# SCH_open_temperature_sensor_2023-12-14.net
KiCad netlist of a schematic drawn in EasyEDA
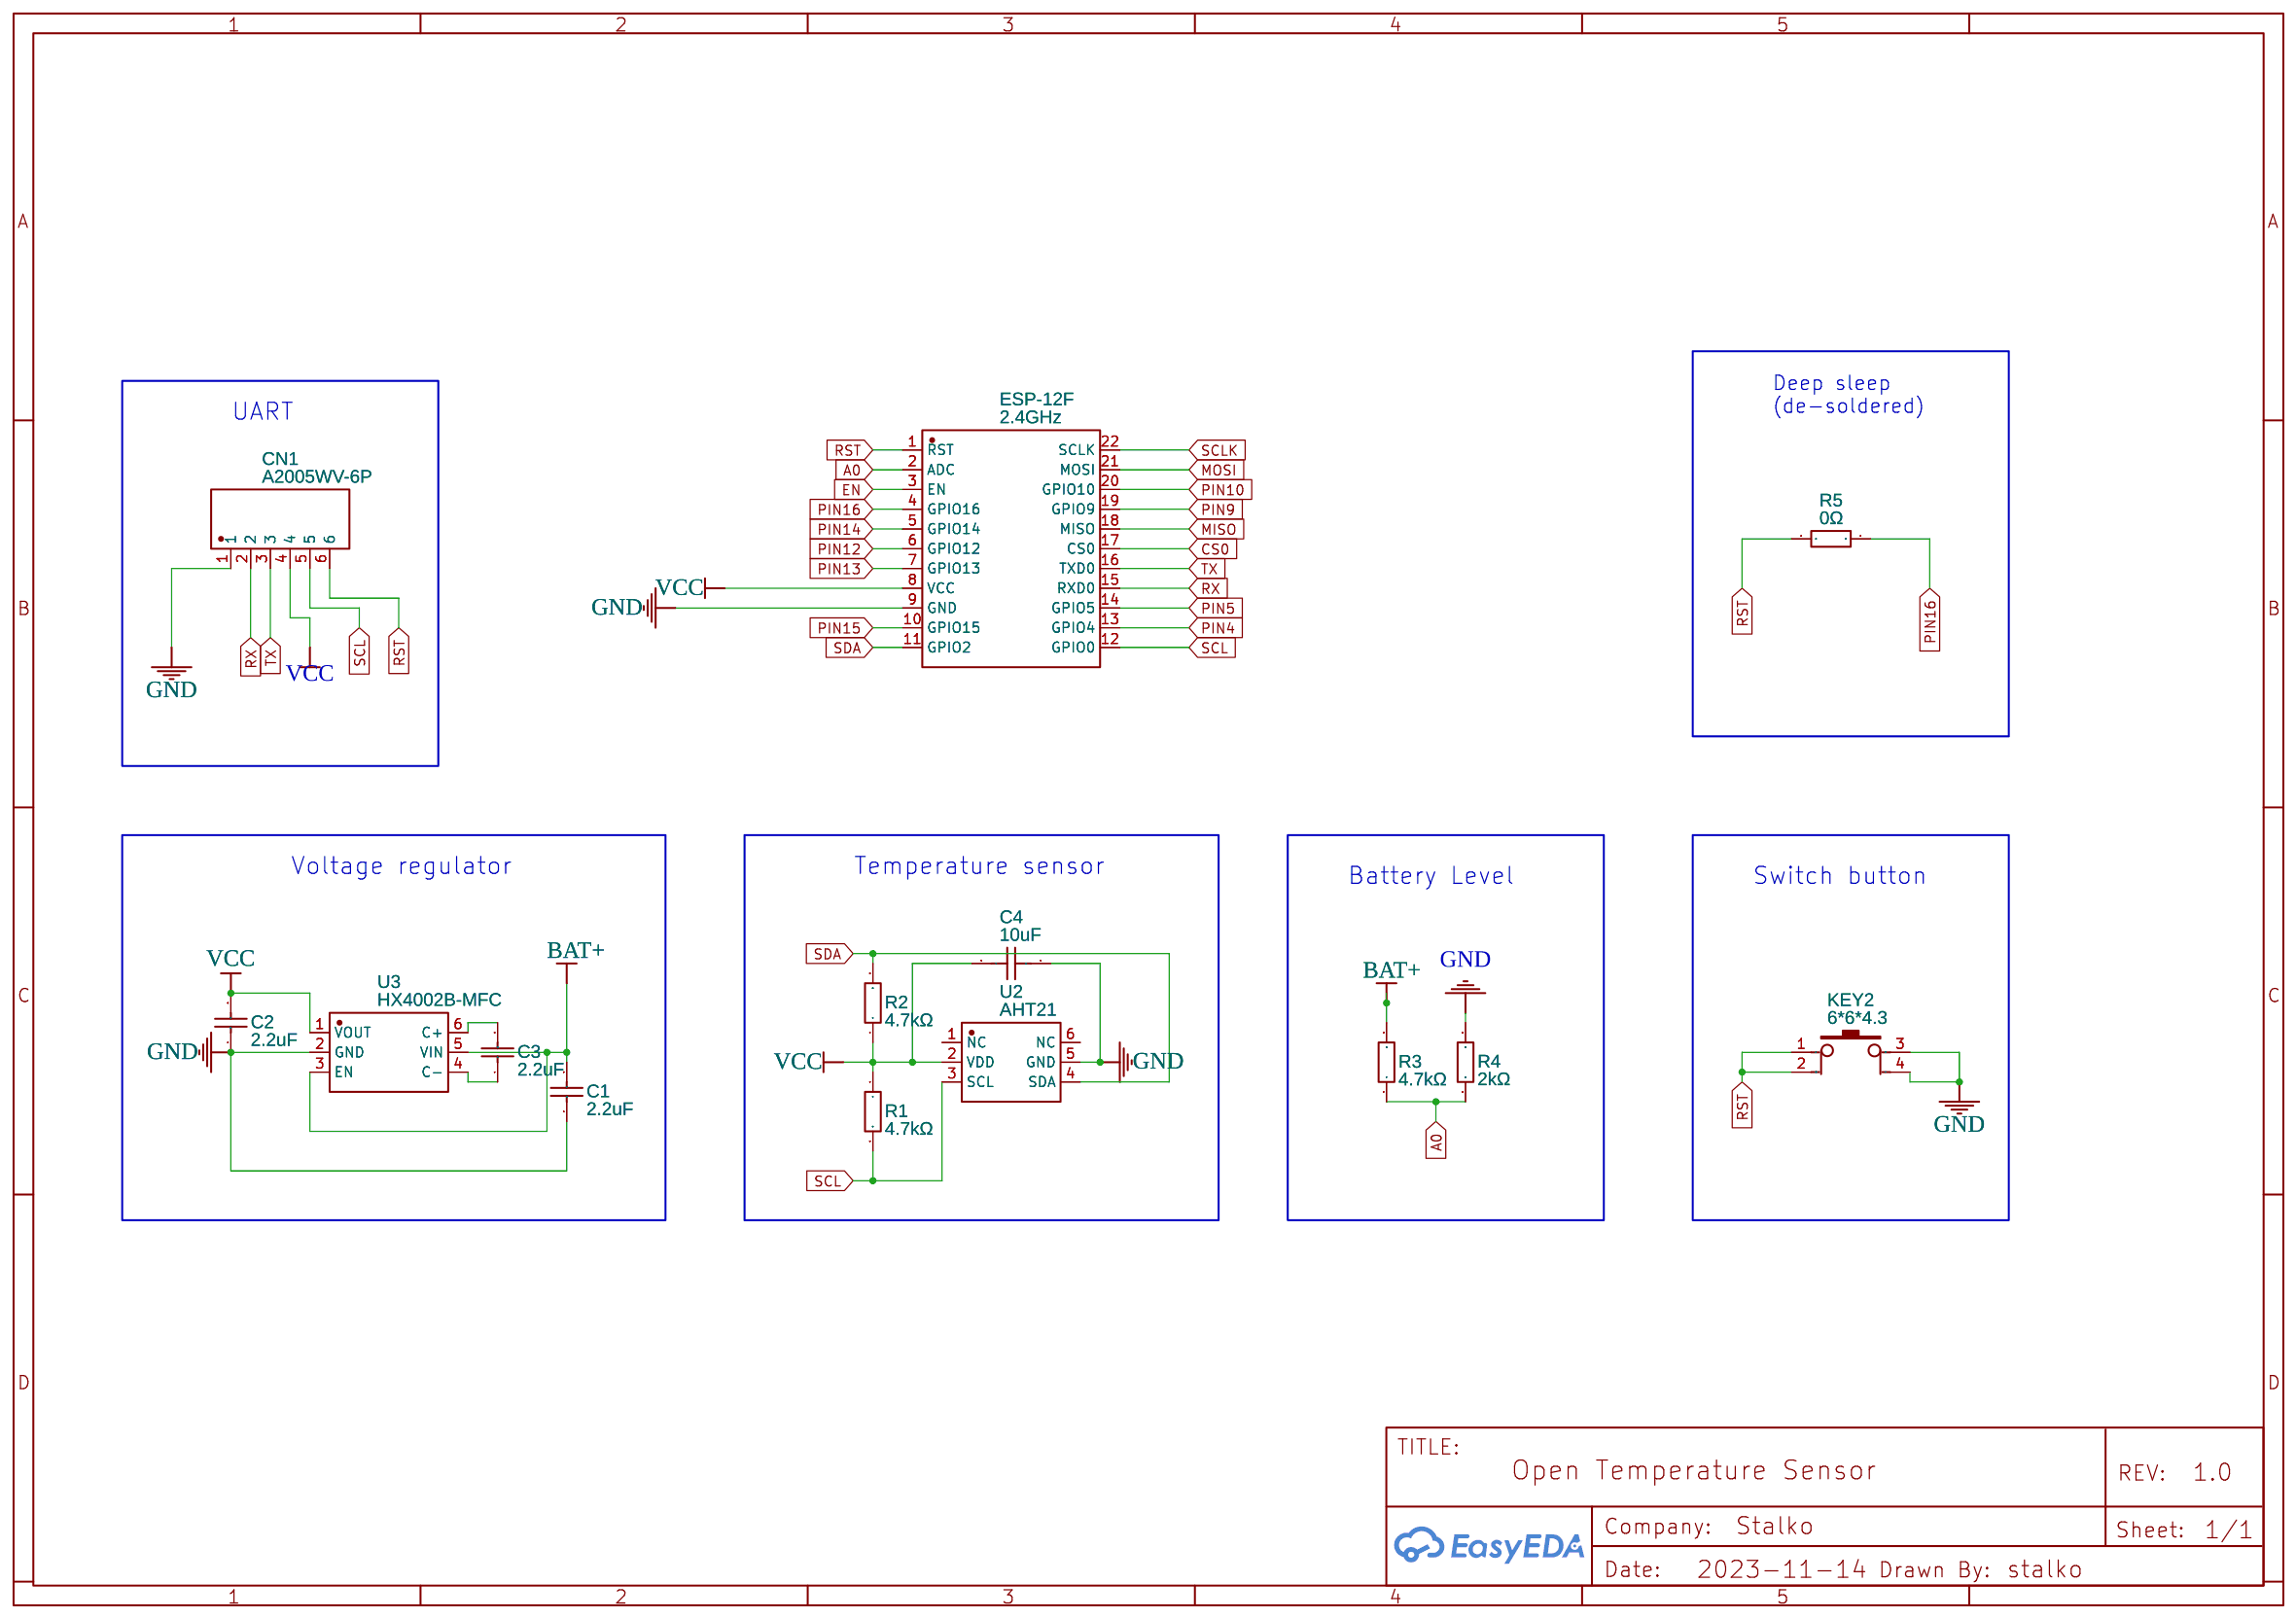
[diagram p0: schematic sheet]

(export (version "E")
  (design (tool "Eeschema 10.0.6"))
  (components
    (comp (ref "C1")
      (value "2.2uF")
      (fields
        (field (name "Manufacturer Part") "CC0805ZKY5V8BB225")
        (field (name "Manufacturer") "YAGEO(国巨)")
      )
      (libsource (lib "") (part "CC0805ZKY5V8BB225"))
    )
    (comp (ref "C2")
      (value "2.2uF")
      (fields
        (field (name "Manufacturer Part") "CC0805ZKY5V8BB225")
        (field (name "Manufacturer") "YAGEO(国巨)")
      )
      (libsource (lib "") (part "CC0805ZKY5V8BB225"))
    )
    (comp (ref "C3")
      (value "2.2uF")
      (fields
        (field (name "Manufacturer Part") "CC0805ZKY5V8BB225")
        (field (name "Manufacturer") "YAGEO(国巨)")
      )
      (libsource (lib "") (part "CC0805ZKY5V8BB225"))
    )
    (comp (ref "C4")
      (value "10uF")
      (fields
        (field (name "Manufacturer Part") "CC0805KKX7R7BB106")
        (field (name "Manufacturer") "YAGEO(国巨)")
      )
      (libsource (lib "") (part "CC0805KKX7R7BB106"))
    )
    (comp (ref "CN1")
      (value "A2005WV-6P")
      (fields (field (name "Manufacturer") "CJT(长江连接器)"))
      (libsource (lib "") (part "A2005WV-6P"))
    )
    (comp (ref "ESP-12F")
      (value "2.4GHz")
      (fields
        (field (name "Manufacturer Part") "ESP-12F(ESP8266MOD)")
        (field (name "Manufacturer") "Ai-Thinker(安信可)")
      )
      (libsource (lib "") (part "ESP-12F(ESP8266MOD)"))
    )
    (comp (ref "KEY2")
      (value "6*6*4.3")
      (fields (field (name "Manufacturer") "ReliaPro"))
      (libsource (lib "") (part "6*6*4.3"))
    )
    (comp (ref "R1")
      (value "4.7kΩ")
      (fields (field (name "Manufacturer Part") "RMC08054.7K5%N") (field (name "Manufacturer") "Tyohm(幸亚电阻)"))
      (libsource (lib "") (part "RMC08054.7K5%N_2"))
    )
    (comp (ref "R2")
      (value "4.7kΩ")
      (fields (field (name "Manufacturer Part") "RMC08054.7K5%N") (field (name "Manufacturer") "Tyohm(幸亚电阻)"))
      (libsource (lib "") (part "RMC08054.7K5%N"))
    )
    (comp (ref "R3")
      (value "4.7kΩ")
      (fields (field (name "Manufacturer Part") "RMC08054.7K5%N") (field (name "Manufacturer") "Tyohm(幸亚电阻)"))
      (libsource (lib "") (part "RMC08054.7K5%N"))
    )
    (comp (ref "R4")
      (value "2kΩ")
      (fields (field (name "Manufacturer Part") "CR0805F82371G") (field (name "Manufacturer") "LIZ(丽智电子)"))
      (libsource (lib "") (part "CR0805F82371G"))
    )
    (comp (ref "R5")
      (value "0Ω")
      (fields (field (name "Manufacturer Part") "RMC08054.7K5%N") (field (name "Manufacturer") "Tyohm(幸亚电阻)"))
      (libsource (lib "") (part "RMC08054.7K5%N_1"))
    )
    (comp (ref "U2")
      (value "AHT21")
      (fields (field (name "Manufacturer") "广州奥松"))
      (libsource (lib "") (part "AHT21"))
    )
    (comp (ref "U3") (value "HX4002B-MFC") (libsource (lib "") (part "HX4002B-MFC")))
  )
  (nets
    (net (code "1") (name "A0") (class "Default")
      (node (ref "ESP-12F") (pin "2") (pinfunction "ADC_2") (pintype "unspecified"))
      (node (ref "R3") (pin "1") (pinfunction "1_1") (pintype "unspecified"))
      (node (ref "R4") (pin "1") (pinfunction "1_1") (pintype "input"))
    )
    (net (code "2") (name "BAT+") (class "Default")
      (node (ref "C1") (pin "2") (pinfunction "2_2") (pintype "input"))
      (node (ref "R3") (pin "2") (pinfunction "2_2") (pintype "unspecified"))
      (node (ref "U3") (pin "3") (pinfunction "EN_3") (pintype "unspecified"))
      (node (ref "U3") (pin "5") (pinfunction "VIN_5") (pintype "unspecified"))
    )
    (net (code "3") (name "CS0") (class "Default")
      (node (ref "ESP-12F") (pin "17") (pinfunction "CS0_17") (pintype "unspecified"))
    )
    (net (code "4") (name "EN") (class "Default")
      (node (ref "ESP-12F") (pin "3") (pinfunction "EN_3") (pintype "unspecified"))
    )
    (net (code "5") (name "GND") (class "Default")
      (node (ref "C1") (pin "1") (pinfunction "1_1") (pintype "input"))
      (node (ref "C2") (pin "1") (pinfunction "1_1") (pintype "input"))
      (node (ref "C4") (pin "1") (pinfunction "1_1") (pintype "unspecified"))
      (node (ref "CN1") (pin "1") (pinfunction "1_1") (pintype "unspecified"))
      (node (ref "ESP-12F") (pin "9") (pinfunction "GND_9") (pintype "unspecified"))
      (node (ref "KEY2") (pin "3") (pinfunction "3_3") (pintype "input"))
      (node (ref "KEY2") (pin "4") (pinfunction "4_4") (pintype "input"))
      (node (ref "R4") (pin "2") (pinfunction "2_2") (pintype "input"))
      (node (ref "U2") (pin "5") (pinfunction "GND_5") (pintype "unspecified"))
      (node (ref "U3") (pin "2") (pinfunction "GND_2") (pintype "unspecified"))
    )
    (net (code "6") (name "MISO") (class "Default")
      (node (ref "ESP-12F") (pin "18") (pinfunction "MISO_18") (pintype "unspecified"))
    )
    (net (code "7") (name "MOSI") (class "Default")
      (node (ref "ESP-12F") (pin "21") (pinfunction "MOSI_21") (pintype "unspecified"))
    )
    (net (code "8") (name "Net-(U3-C+)") (class "Default")
      (node (ref "C3") (pin "2") (pinfunction "2_2") (pintype "input"))
      (node (ref "U3") (pin "6") (pinfunction "C+_6") (pintype "unspecified"))
    )
    (net (code "9") (name "Net-(U3-C-)") (class "Default")
      (node (ref "C3") (pin "1") (pinfunction "1_1") (pintype "input"))
      (node (ref "U3") (pin "4") (pinfunction "C-_4") (pintype "unspecified"))
    )
    (net (code "10") (name "PIN4") (class "Default")
      (node (ref "ESP-12F") (pin "13") (pinfunction "GPIO4_13") (pintype "unspecified"))
    )
    (net (code "11") (name "PIN5") (class "Default")
      (node (ref "ESP-12F") (pin "14") (pinfunction "GPIO5_14") (pintype "unspecified"))
    )
    (net (code "12") (name "PIN9") (class "Default")
      (node (ref "ESP-12F") (pin "19") (pinfunction "GPIO9_19") (pintype "unspecified"))
    )
    (net (code "13") (name "PIN10") (class "Default")
      (node (ref "ESP-12F") (pin "20") (pinfunction "GPIO10_20") (pintype "unspecified"))
    )
    (net (code "14") (name "PIN12") (class "Default")
      (node (ref "ESP-12F") (pin "6") (pinfunction "GPIO12_6") (pintype "unspecified"))
    )
    (net (code "15") (name "PIN13") (class "Default")
      (node (ref "ESP-12F") (pin "7") (pinfunction "GPIO13_7") (pintype "unspecified"))
    )
    (net (code "16") (name "PIN14") (class "Default")
      (node (ref "ESP-12F") (pin "5") (pinfunction "GPIO14_5") (pintype "unspecified"))
    )
    (net (code "17") (name "PIN15") (class "Default")
      (node (ref "ESP-12F") (pin "10") (pinfunction "GPIO15_10") (pintype "unspecified"))
    )
    (net (code "18") (name "PIN16") (class "Default")
      (node (ref "ESP-12F") (pin "4") (pinfunction "GPIO16_4") (pintype "unspecified"))
      (node (ref "R5") (pin "1") (pinfunction "1_1") (pintype "unspecified"))
    )
    (net (code "19") (name "RST") (class "Default")
      (node (ref "CN1") (pin "6") (pinfunction "6_6") (pintype "unspecified"))
      (node (ref "ESP-12F") (pin "1") (pinfunction "RST_1") (pintype "unspecified"))
      (node (ref "KEY2") (pin "1") (pinfunction "1_1") (pintype "input"))
      (node (ref "KEY2") (pin "2") (pinfunction "2_2") (pintype "input"))
      (node (ref "R5") (pin "2") (pinfunction "2_2") (pintype "unspecified"))
    )
    (net (code "20") (name "RX") (class "Default")
      (node (ref "CN1") (pin "2") (pinfunction "2_2") (pintype "unspecified"))
      (node (ref "ESP-12F") (pin "15") (pinfunction "RXD0_15") (pintype "unspecified"))
    )
    (net (code "21") (name "SCL") (class "Default")
      (node (ref "CN1") (pin "5") (pinfunction "5_5") (pintype "unspecified"))
      (node (ref "ESP-12F") (pin "12") (pinfunction "GPIO0_12") (pintype "unspecified"))
      (node (ref "R1") (pin "2") (pinfunction "2_2") (pintype "unspecified"))
      (node (ref "U2") (pin "3") (pinfunction "SCL_3") (pintype "unspecified"))
    )
    (net (code "22") (name "SCLK") (class "Default")
      (node (ref "ESP-12F") (pin "22") (pinfunction "SCLK_22") (pintype "unspecified"))
    )
    (net (code "23") (name "SDA") (class "Default")
      (node (ref "ESP-12F") (pin "11") (pinfunction "GPIO2_11") (pintype "unspecified"))
      (node (ref "R2") (pin "2") (pinfunction "2_2") (pintype "unspecified"))
      (node (ref "U2") (pin "4") (pinfunction "SDA_4") (pintype "unspecified"))
    )
    (net (code "24") (name "TX") (class "Default")
      (node (ref "CN1") (pin "3") (pinfunction "3_3") (pintype "unspecified"))
      (node (ref "ESP-12F") (pin "16") (pinfunction "TXD0_16") (pintype "unspecified"))
    )
    (net (code "25") (name "VCC") (class "Default")
      (node (ref "C2") (pin "2") (pinfunction "2_2") (pintype "input"))
      (node (ref "C4") (pin "2") (pinfunction "2_2") (pintype "unspecified"))
      (node (ref "CN1") (pin "4") (pinfunction "4_4") (pintype "unspecified"))
      (node (ref "ESP-12F") (pin "8") (pinfunction "VCC_8") (pintype "unspecified"))
      (node (ref "R1") (pin "1") (pinfunction "1_1") (pintype "unspecified"))
      (node (ref "R2") (pin "1") (pinfunction "1_1") (pintype "unspecified"))
      (node (ref "U2") (pin "2") (pinfunction "VDD_2") (pintype "unspecified"))
      (node (ref "U3") (pin "1") (pinfunction "VOUT_1") (pintype "unspecified"))
    )
    (net (code "26") (name "unconnected-(U2-NC-Pad1)") (class "Default")
      (node (ref "U2") (pin "1") (pinfunction "NC_1") (pintype "unspecified"))
    )
    (net (code "27") (name "unconnected-(U2-NC-Pad6)") (class "Default")
      (node (ref "U2") (pin "6") (pinfunction "NC_6") (pintype "unspecified"))
    )
  )
)
